# gleis-a-3.net
KiCad netlist of a schematic drawn in EAGLE
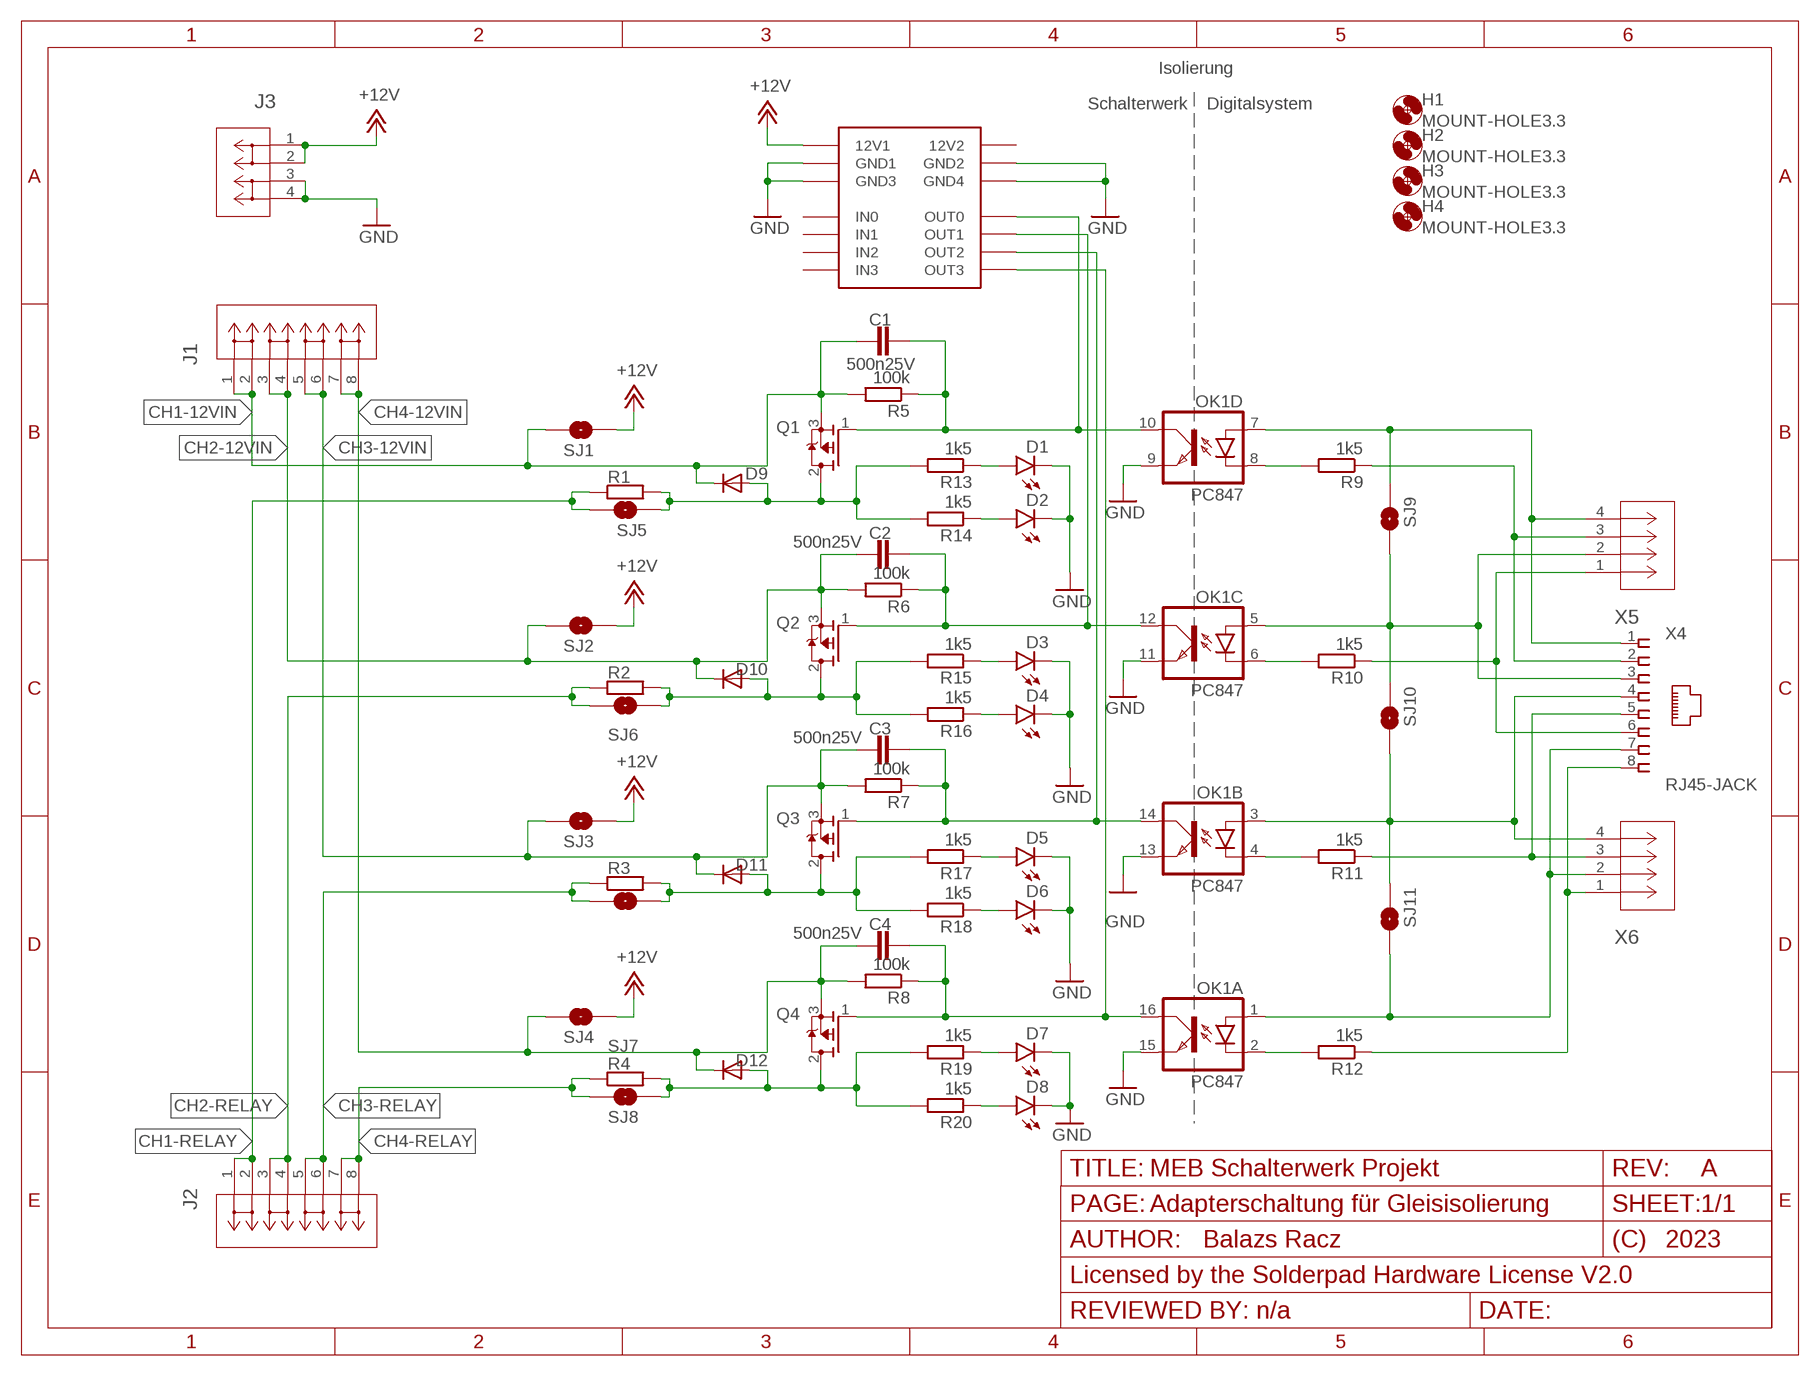
[diagram p0: schematic, sheet 1]

(export (version "E")
  (design (tool "Eeschema 10.0.6"))
  (components
    (comp (ref "C1")
      (value "500n25V")
      (footprint "eagle-import:C0805")
      (libsource (lib "eagle-import") (part "C-EUC0805"))
    )
    (comp (ref "C2")
      (value "500n25V")
      (footprint "eagle-import:C0805")
      (libsource (lib "eagle-import") (part "C-EUC0805"))
    )
    (comp (ref "C3")
      (value "500n25V")
      (footprint "eagle-import:C0805")
      (libsource (lib "eagle-import") (part "C-EUC0805"))
    )
    (comp (ref "C4")
      (value "500n25V")
      (footprint "eagle-import:C0805")
      (libsource (lib "eagle-import") (part "C-EUC0805"))
    )
    (comp (ref "D1")
      (value "LEDCHIPLED_0603")
      (footprint "eagle-import:CHIPLED_0603")
      (libsource (lib "eagle-import") (part "LEDCHIPLED_0603"))
    )
    (comp (ref "D2")
      (value "LEDHEADER")
      (footprint "eagle-import:LEDHEADER")
      (libsource (lib "eagle-import") (part "LEDHEADER"))
    )
    (comp (ref "D3")
      (value "LEDCHIPLED_0603")
      (footprint "eagle-import:CHIPLED_0603")
      (libsource (lib "eagle-import") (part "LEDCHIPLED_0603"))
    )
    (comp (ref "D4")
      (value "LEDHEADER")
      (footprint "eagle-import:LEDHEADER")
      (libsource (lib "eagle-import") (part "LEDHEADER"))
    )
    (comp (ref "D5")
      (value "LEDCHIPLED_0603")
      (footprint "eagle-import:CHIPLED_0603")
      (libsource (lib "eagle-import") (part "LEDCHIPLED_0603"))
    )
    (comp (ref "D6")
      (value "LEDHEADER")
      (footprint "eagle-import:LEDHEADER")
      (libsource (lib "eagle-import") (part "LEDHEADER"))
    )
    (comp (ref "D7")
      (value "LEDCHIPLED_0603")
      (footprint "eagle-import:CHIPLED_0603")
      (libsource (lib "eagle-import") (part "LEDCHIPLED_0603"))
    )
    (comp (ref "D8")
      (value "LEDHEADER")
      (footprint "eagle-import:LEDHEADER")
      (libsource (lib "eagle-import") (part "LEDHEADER"))
    )
    (comp (ref "D9")
      (value "DIODEDO-214AA-NODOC")
      (footprint "eagle-import:DO214AA-NODOC")
      (libsource (lib "eagle-import") (part "DIODEDO-214AA-NODOC"))
    )
    (comp (ref "D10")
      (value "DIODEDO-214AA-NODOC")
      (footprint "eagle-import:DO214AA-NODOC")
      (libsource (lib "eagle-import") (part "DIODEDO-214AA-NODOC"))
    )
    (comp (ref "D11")
      (value "DIODEDO-214AA-NODOC")
      (footprint "eagle-import:DO214AA-NODOC")
      (libsource (lib "eagle-import") (part "DIODEDO-214AA-NODOC"))
    )
    (comp (ref "D12")
      (value "DIODEDO-214AA-NODOC")
      (footprint "eagle-import:DO214AA-NODOC")
      (libsource (lib "eagle-import") (part "DIODEDO-214AA-NODOC"))
    )
    (comp (ref "H1")
      (value "MOUNT-HOLE3.3")
      (footprint "eagle-import:3,3")
      (libsource (lib "eagle-import") (part "MOUNT-HOLE3.3"))
    )
    (comp (ref "H2")
      (value "MOUNT-HOLE3.3")
      (footprint "eagle-import:3,3")
      (libsource (lib "eagle-import") (part "MOUNT-HOLE3.3"))
    )
    (comp (ref "H3")
      (value "MOUNT-HOLE3.3")
      (footprint "eagle-import:3,3")
      (libsource (lib "eagle-import") (part "MOUNT-HOLE3.3"))
    )
    (comp (ref "H4")
      (value "MOUNT-HOLE3.3")
      (footprint "eagle-import:3,3")
      (libsource (lib "eagle-import") (part "MOUNT-HOLE3.3"))
    )
    (comp (ref "J1")
      (value "PHNX_4P_508CONN_1017493")
      (footprint "eagle-import:PHNX_4P_508")
      (fields
        (field (name "MANUFACTURER_PART_NUMBER") "1017505")
        (field (name "COPYRIGHT") "Copyright (C) 2023 Ultra Librarian. All rights reserved.")
      )
      (libsource (lib "eagle-import") (part "PHNX_4P_508CONN_1017493"))
    )
    (comp (ref "J2")
      (value "PHNX_4P_508CONN_1017493")
      (footprint "eagle-import:PHNX_4P_508")
      (fields
        (field (name "MANUFACTURER_PART_NUMBER") "1017505")
        (field (name "COPYRIGHT") "Copyright (C) 2023 Ultra Librarian. All rights reserved.")
      )
      (libsource (lib "eagle-import") (part "PHNX_4P_508CONN_1017493"))
    )
    (comp (ref "J3")
      (value "PHNX_2P_508CONN_1017491")
      (footprint "eagle-import:PHNX_2P_508")
      (fields
        (field (name "MANUFACTURER_PART_NUMBER") "1017503")
        (field (name "COPYRIGHT") "Copyright (C) 2023 Ultra Librarian. All rights reserved.")
      )
      (libsource (lib "eagle-import") (part "PHNX_2P_508CONN_1017491"))
    )
    (comp (ref "OK1")
      (value "PC847")
      (footprint "eagle-import:DIL16")
      (libsource (lib "eagle-import") (part "PC847"))
    )
    (comp (ref "Q1")
      (value "P-MOSFET")
      (footprint "eagle-import:DPAK-2")
      (fields (field (name "MANUFACTURER") "Infineon"))
      (libsource (lib "eagle-import") (part "P-MOSFET"))
    )
    (comp (ref "Q2")
      (value "P-MOSFET")
      (footprint "eagle-import:DPAK-2")
      (fields (field (name "MANUFACTURER") "Infineon"))
      (libsource (lib "eagle-import") (part "P-MOSFET"))
    )
    (comp (ref "Q3")
      (value "P-MOSFET")
      (footprint "eagle-import:DPAK-2")
      (fields (field (name "MANUFACTURER") "Infineon"))
      (libsource (lib "eagle-import") (part "P-MOSFET"))
    )
    (comp (ref "Q4")
      (value "P-MOSFET")
      (footprint "eagle-import:DPAK-2")
      (fields (field (name "MANUFACTURER") "Infineon"))
      (libsource (lib "eagle-import") (part "P-MOSFET"))
    )
    (comp (ref "R1")
      (value "R-EU_VTA52")
      (footprint "eagle-import:VTA52")
      (libsource (lib "eagle-import") (part "R-EU_VTA52"))
    )
    (comp (ref "R2")
      (value "R-EU_VTA52")
      (footprint "eagle-import:VTA52")
      (libsource (lib "eagle-import") (part "R-EU_VTA52"))
    )
    (comp (ref "R3")
      (value "R-EU_VTA52")
      (footprint "eagle-import:VTA52")
      (libsource (lib "eagle-import") (part "R-EU_VTA52"))
    )
    (comp (ref "R4")
      (value "R-EU_VTA52")
      (footprint "eagle-import:VTA52")
      (libsource (lib "eagle-import") (part "R-EU_VTA52"))
    )
    (comp (ref "R5")
      (value "100k")
      (footprint "eagle-import:R0805")
      (libsource (lib "eagle-import") (part "R-EU_R0805"))
    )
    (comp (ref "R6")
      (value "100k")
      (footprint "eagle-import:R0805")
      (libsource (lib "eagle-import") (part "R-EU_R0805"))
    )
    (comp (ref "R7")
      (value "100k")
      (footprint "eagle-import:R0805")
      (libsource (lib "eagle-import") (part "R-EU_R0805"))
    )
    (comp (ref "R8")
      (value "100k")
      (footprint "eagle-import:R0805")
      (libsource (lib "eagle-import") (part "R-EU_R0805"))
    )
    (comp (ref "R9")
      (value "1k5")
      (footprint "eagle-import:R0805")
      (libsource (lib "eagle-import") (part "R-EU_R0805"))
    )
    (comp (ref "R10")
      (value "1k5")
      (footprint "eagle-import:R0805")
      (libsource (lib "eagle-import") (part "R-EU_R0805"))
    )
    (comp (ref "R11")
      (value "1k5")
      (footprint "eagle-import:R0805")
      (libsource (lib "eagle-import") (part "R-EU_R0805"))
    )
    (comp (ref "R12")
      (value "1k5")
      (footprint "eagle-import:R0805")
      (libsource (lib "eagle-import") (part "R-EU_R0805"))
    )
    (comp (ref "R13")
      (value "1k5")
      (footprint "eagle-import:R0805")
      (libsource (lib "eagle-import") (part "R-EU_R0805"))
    )
    (comp (ref "R14")
      (value "1k5")
      (footprint "eagle-import:R0805")
      (libsource (lib "eagle-import") (part "R-EU_R0805"))
    )
    (comp (ref "R15")
      (value "1k5")
      (footprint "eagle-import:R0805")
      (libsource (lib "eagle-import") (part "R-EU_R0805"))
    )
    (comp (ref "R16")
      (value "1k5")
      (footprint "eagle-import:R0805")
      (libsource (lib "eagle-import") (part "R-EU_R0805"))
    )
    (comp (ref "R17")
      (value "1k5")
      (footprint "eagle-import:R0805")
      (libsource (lib "eagle-import") (part "R-EU_R0805"))
    )
    (comp (ref "R18")
      (value "1k5")
      (footprint "eagle-import:R0805")
      (libsource (lib "eagle-import") (part "R-EU_R0805"))
    )
    (comp (ref "R19")
      (value "1k5")
      (footprint "eagle-import:R0805")
      (libsource (lib "eagle-import") (part "R-EU_R0805"))
    )
    (comp (ref "R20")
      (value "1k5")
      (footprint "eagle-import:R0805")
      (libsource (lib "eagle-import") (part "R-EU_R0805"))
    )
    (comp (ref "SJ1")
      (value "SJRND2")
      (footprint "eagle-import:SJ_RND2")
      (libsource (lib "eagle-import") (part "SJRND2"))
    )
    (comp (ref "SJ2")
      (value "SJRND2")
      (footprint "eagle-import:SJ_RND2")
      (libsource (lib "eagle-import") (part "SJRND2"))
    )
    (comp (ref "SJ3")
      (value "SJRND2")
      (footprint "eagle-import:SJ_RND2")
      (libsource (lib "eagle-import") (part "SJRND2"))
    )
    (comp (ref "SJ4")
      (value "SJRND2")
      (footprint "eagle-import:SJ_RND2")
      (libsource (lib "eagle-import") (part "SJRND2"))
    )
    (comp (ref "SJ5")
      (value "SJRND2")
      (footprint "eagle-import:SJ_RND2")
      (libsource (lib "eagle-import") (part "SJRND2"))
    )
    (comp (ref "SJ6")
      (value "SJRND2")
      (footprint "eagle-import:SJ_RND2")
      (libsource (lib "eagle-import") (part "SJRND2"))
    )
    (comp (ref "SJ7")
      (value "SJRND2")
      (footprint "eagle-import:SJ_RND2")
      (libsource (lib "eagle-import") (part "SJRND2"))
    )
    (comp (ref "SJ8")
      (value "SJRND2")
      (footprint "eagle-import:SJ_RND2")
      (libsource (lib "eagle-import") (part "SJRND2"))
    )
    (comp (ref "SJ9")
      (value "SJRND2")
      (footprint "eagle-import:SJ_RND2")
      (libsource (lib "eagle-import") (part "SJRND2"))
    )
    (comp (ref "SJ10")
      (value "SJRND2")
      (footprint "eagle-import:SJ_RND2")
      (libsource (lib "eagle-import") (part "SJRND2"))
    )
    (comp (ref "SJ11")
      (value "SJRND2")
      (footprint "eagle-import:SJ_RND2")
      (libsource (lib "eagle-import") (part "SJRND2"))
    )
    (comp (ref "X2")
      (value "IO-HAT")
      (footprint "eagle-import:IOBOARD")
      (libsource (lib "eagle-import") (part "IO-HAT"))
    )
    (comp (ref "X4")
      (value "RJ45-JACK")
      (footprint "eagle-import:RJ45-PULSE-E5J88")
      (libsource (lib "eagle-import") (part "RJ45-JACKRJ45-PULSE-E5J00"))
    )
    (comp (ref "X5")
      (value "PHNX_4P_350CONN_1984989_PXC")
      (footprint "eagle-import:PHNX_4P_350")
      (fields
        (field (name "MANUFACTURER_PART_NUMBER") "1984989")
        (field (name "COPYRIGHT") "Copyright (C) 2023 Ultra Librarian. All rights reserved.")
      )
      (libsource (lib "eagle-import") (part "PHNX_4P_350CONN_1984989_PXC"))
    )
    (comp (ref "X6")
      (value "PHNX_4P_350CONN_1984989_PXC")
      (footprint "eagle-import:PHNX_4P_350")
      (fields
        (field (name "MANUFACTURER_PART_NUMBER") "1984989")
        (field (name "COPYRIGHT") "Copyright (C) 2023 Ultra Librarian. All rights reserved.")
      )
      (libsource (lib "eagle-import") (part "PHNX_4P_350CONN_1984989_PXC"))
    )
  )
  (nets
    (net (code "1") (name "+12V") (class "Default")
      (node (ref "J3") (pin "1") (pinfunction "1_1") (pintype "passive"))
      (node (ref "J3") (pin "2") (pinfunction "2_2") (pintype "passive"))
      (node (ref "SJ1") (pin "P$2") (pinfunction "2_P$2") (pintype "passive"))
      (node (ref "SJ2") (pin "P$2") (pinfunction "2_P$2") (pintype "passive"))
      (node (ref "SJ3") (pin "P$2") (pinfunction "2_P$2") (pintype "passive"))
      (node (ref "SJ4") (pin "P$2") (pinfunction "2_P$2") (pintype "passive"))
      (node (ref "X2") (pin "P$1") (pinfunction "12V1_P$1") (pintype "power_in"))
    )
    (net (code "2") (name "/12V2") (class "Default")
      (node (ref "X2") (pin "P$22") (pinfunction "12V2_P$22") (pintype "power_in"))
    )
    (net (code "3") (name "CH1-12VIN") (class "Default")
      (node (ref "C1") (pin "1") (pinfunction "1_1") (pintype "passive"))
      (node (ref "D9") (pin "C") (pinfunction "C_C") (pintype "passive"))
      (node (ref "J1") (pin "1") (pinfunction "1_1") (pintype "passive"))
      (node (ref "J1") (pin "2") (pinfunction "2_2") (pintype "passive"))
      (node (ref "Q1") (pin "3") (pinfunction "S_3") (pintype "passive"))
      (node (ref "R5") (pin "2") (pinfunction "2_2") (pintype "passive"))
      (node (ref "SJ1") (pin "P$1") (pinfunction "1_P$1") (pintype "passive"))
    )
    (net (code "4") (name "CH1-RELAY") (class "Default")
      (node (ref "J2") (pin "1") (pinfunction "1_1") (pintype "passive"))
      (node (ref "J2") (pin "2") (pinfunction "2_2") (pintype "passive"))
      (node (ref "R1") (pin "1") (pinfunction "1_1") (pintype "passive"))
      (node (ref "SJ5") (pin "P$1") (pinfunction "1_P$1") (pintype "passive"))
    )
    (net (code "5") (name "CH2-12VIN") (class "Default")
      (node (ref "C2") (pin "1") (pinfunction "1_1") (pintype "passive"))
      (node (ref "D10") (pin "C") (pinfunction "C_C") (pintype "passive"))
      (node (ref "J1") (pin "3") (pinfunction "3_3") (pintype "passive"))
      (node (ref "J1") (pin "4") (pinfunction "4_4") (pintype "passive"))
      (node (ref "Q2") (pin "3") (pinfunction "S_3") (pintype "passive"))
      (node (ref "R6") (pin "2") (pinfunction "2_2") (pintype "passive"))
      (node (ref "SJ2") (pin "P$1") (pinfunction "1_P$1") (pintype "passive"))
    )
    (net (code "6") (name "CH2-RELAY") (class "Default")
      (node (ref "J2") (pin "3") (pinfunction "3_3") (pintype "passive"))
      (node (ref "J2") (pin "4") (pinfunction "4_4") (pintype "passive"))
      (node (ref "R2") (pin "1") (pinfunction "1_1") (pintype "passive"))
      (node (ref "SJ6") (pin "P$1") (pinfunction "1_P$1") (pintype "passive"))
    )
    (net (code "7") (name "CH3-12VIN") (class "Default")
      (node (ref "C3") (pin "1") (pinfunction "1_1") (pintype "passive"))
      (node (ref "D11") (pin "C") (pinfunction "C_C") (pintype "passive"))
      (node (ref "J1") (pin "5") (pinfunction "5_5") (pintype "passive"))
      (node (ref "J1") (pin "6") (pinfunction "6_6") (pintype "passive"))
      (node (ref "Q3") (pin "3") (pinfunction "S_3") (pintype "passive"))
      (node (ref "R7") (pin "2") (pinfunction "2_2") (pintype "passive"))
      (node (ref "SJ3") (pin "P$1") (pinfunction "1_P$1") (pintype "passive"))
    )
    (net (code "8") (name "CH3-RELAY") (class "Default")
      (node (ref "J2") (pin "5") (pinfunction "5_5") (pintype "passive"))
      (node (ref "J2") (pin "6") (pinfunction "6_6") (pintype "passive"))
      (node (ref "R3") (pin "1") (pinfunction "1_1") (pintype "passive"))
      (node (ref "SJ7") (pin "P$1") (pinfunction "1_P$1") (pintype "passive"))
    )
    (net (code "9") (name "CH4-12VIN") (class "Default")
      (node (ref "C4") (pin "1") (pinfunction "1_1") (pintype "passive"))
      (node (ref "D12") (pin "C") (pinfunction "C_C") (pintype "passive"))
      (node (ref "J1") (pin "7") (pinfunction "7_7") (pintype "passive"))
      (node (ref "J1") (pin "8") (pinfunction "8_8") (pintype "passive"))
      (node (ref "Q4") (pin "3") (pinfunction "S_3") (pintype "passive"))
      (node (ref "R8") (pin "2") (pinfunction "2_2") (pintype "passive"))
      (node (ref "SJ4") (pin "P$1") (pinfunction "1_P$1") (pintype "passive"))
    )
    (net (code "10") (name "CH4-RELAY") (class "Default")
      (node (ref "J2") (pin "7") (pinfunction "7_7") (pintype "passive"))
      (node (ref "J2") (pin "8") (pinfunction "8_8") (pintype "passive"))
      (node (ref "R4") (pin "1") (pinfunction "1_1") (pintype "passive"))
      (node (ref "SJ8") (pin "P$1") (pinfunction "1_P$1") (pintype "passive"))
    )
    (net (code "11") (name "GND") (class "Default")
      (node (ref "D1") (pin "C") (pinfunction "C_C") (pintype "passive"))
      (node (ref "D2") (pin "C") (pinfunction "C_C") (pintype "passive"))
      (node (ref "D3") (pin "C") (pinfunction "C_C") (pintype "passive"))
      (node (ref "D4") (pin "C") (pinfunction "C_C") (pintype "passive"))
      (node (ref "D5") (pin "C") (pinfunction "C_C") (pintype "passive"))
      (node (ref "D6") (pin "C") (pinfunction "C_C") (pintype "passive"))
      (node (ref "D7") (pin "C") (pinfunction "C_C") (pintype "passive"))
      (node (ref "D8") (pin "C") (pinfunction "C_C") (pintype "passive"))
      (node (ref "J3") (pin "3") (pinfunction "3_3") (pintype "passive"))
      (node (ref "J3") (pin "4") (pinfunction "4_4") (pintype "passive"))
      (node (ref "OK1") (pin "11") (pinfunction "EMIT_11") (pintype "passive"))
      (node (ref "OK1") (pin "13") (pinfunction "EMIT_13") (pintype "passive"))
      (node (ref "OK1") (pin "15") (pinfunction "EMIT_15") (pintype "passive"))
      (node (ref "OK1") (pin "9") (pinfunction "EMIT_9") (pintype "passive"))
      (node (ref "X2") (pin "P$11") (pinfunction "GND3_P$11") (pintype "power_in"))
      (node (ref "X2") (pin "P$12") (pinfunction "GND4_P$12") (pintype "power_in"))
      (node (ref "X2") (pin "P$2") (pinfunction "GND1_P$2") (pintype "power_in"))
      (node (ref "X2") (pin "P$21") (pinfunction "GND2_P$21") (pintype "power_in"))
    )
    (net (code "12") (name "Net-(D1-PadA)") (class "Default")
      (node (ref "D1") (pin "A") (pinfunction "A_A") (pintype "passive"))
      (node (ref "R13") (pin "1") (pinfunction "1_1") (pintype "passive"))
    )
    (net (code "13") (name "Net-(D2-PadA)") (class "Default")
      (node (ref "D2") (pin "A") (pinfunction "A_A") (pintype "passive"))
      (node (ref "R14") (pin "1") (pinfunction "1_1") (pintype "passive"))
    )
    (net (code "14") (name "Net-(D3-PadA)") (class "Default")
      (node (ref "D3") (pin "A") (pinfunction "A_A") (pintype "passive"))
      (node (ref "R15") (pin "1") (pinfunction "1_1") (pintype "passive"))
    )
    (net (code "15") (name "Net-(D4-PadA)") (class "Default")
      (node (ref "D4") (pin "A") (pinfunction "A_A") (pintype "passive"))
      (node (ref "R16") (pin "1") (pinfunction "1_1") (pintype "passive"))
    )
    (net (code "16") (name "Net-(D5-PadA)") (class "Default")
      (node (ref "D5") (pin "A") (pinfunction "A_A") (pintype "passive"))
      (node (ref "R17") (pin "1") (pinfunction "1_1") (pintype "passive"))
    )
    (net (code "17") (name "Net-(D6-PadA)") (class "Default")
      (node (ref "D6") (pin "A") (pinfunction "A_A") (pintype "passive"))
      (node (ref "R18") (pin "1") (pinfunction "1_1") (pintype "passive"))
    )
    (net (code "18") (name "Net-(D7-PadA)") (class "Default")
      (node (ref "D7") (pin "A") (pinfunction "A_A") (pintype "passive"))
      (node (ref "R19") (pin "1") (pinfunction "1_1") (pintype "passive"))
    )
    (net (code "19") (name "Net-(D8-PadA)") (class "Default")
      (node (ref "D8") (pin "A") (pinfunction "A_A") (pintype "passive"))
      (node (ref "R20") (pin "1") (pinfunction "1_1") (pintype "passive"))
    )
    (net (code "20") (name "Net-(OK1A-A)") (class "Default")
      (node (ref "OK1") (pin "1") (pinfunction "A_1") (pintype "passive"))
      (node (ref "SJ11") (pin "P$1") (pinfunction "1_P$1") (pintype "passive"))
      (node (ref "X4") (pin "7") (pinfunction "7_7") (pintype "passive"))
      (node (ref "X6") (pin "2") (pinfunction "2_2") (pintype "passive"))
    )
    (net (code "21") (name "Net-(OK1A-C)") (class "Default")
      (node (ref "OK1") (pin "2") (pinfunction "C_2") (pintype "passive"))
      (node (ref "R12") (pin "2") (pinfunction "2_2") (pintype "passive"))
    )
    (net (code "22") (name "Net-(OK1A-COL)") (class "Default")
      (node (ref "C4") (pin "2") (pinfunction "2_2") (pintype "passive"))
      (node (ref "OK1") (pin "16") (pinfunction "COL_16") (pintype "passive"))
      (node (ref "Q4") (pin "1") (pinfunction "G_1") (pintype "passive"))
      (node (ref "R8") (pin "1") (pinfunction "1_1") (pintype "passive"))
      (node (ref "X2") (pin "P$17") (pinfunction "OUT3_P$17") (pintype "open_collector"))
    )
    (net (code "23") (name "Net-(OK1B-A)") (class "Default")
      (node (ref "OK1") (pin "3") (pinfunction "A_3") (pintype "passive"))
      (node (ref "SJ10") (pin "P$1") (pinfunction "1_P$1") (pintype "passive"))
      (node (ref "SJ11") (pin "P$2") (pinfunction "2_P$2") (pintype "passive"))
      (node (ref "X4") (pin "4") (pinfunction "4_4") (pintype "passive"))
      (node (ref "X6") (pin "4") (pinfunction "4_4") (pintype "passive"))
    )
    (net (code "24") (name "Net-(OK1B-C)") (class "Default")
      (node (ref "OK1") (pin "4") (pinfunction "C_4") (pintype "passive"))
      (node (ref "R11") (pin "2") (pinfunction "2_2") (pintype "passive"))
    )
    (net (code "25") (name "Net-(OK1B-COL)") (class "Default")
      (node (ref "C3") (pin "2") (pinfunction "2_2") (pintype "passive"))
      (node (ref "OK1") (pin "14") (pinfunction "COL_14") (pintype "passive"))
      (node (ref "Q3") (pin "1") (pinfunction "G_1") (pintype "passive"))
      (node (ref "R7") (pin "1") (pinfunction "1_1") (pintype "passive"))
      (node (ref "X2") (pin "P$18") (pinfunction "OUT2_P$18") (pintype "open_collector"))
    )
    (net (code "26") (name "Net-(OK1C-A)") (class "Default")
      (node (ref "OK1") (pin "5") (pinfunction "A_5") (pintype "passive"))
      (node (ref "SJ10") (pin "P$2") (pinfunction "2_P$2") (pintype "passive"))
      (node (ref "SJ9") (pin "P$1") (pinfunction "1_P$1") (pintype "passive"))
      (node (ref "X4") (pin "3") (pinfunction "3_3") (pintype "passive"))
      (node (ref "X5") (pin "2") (pinfunction "2_2") (pintype "passive"))
    )
    (net (code "27") (name "Net-(OK1C-C)") (class "Default")
      (node (ref "OK1") (pin "6") (pinfunction "C_6") (pintype "passive"))
      (node (ref "R10") (pin "2") (pinfunction "2_2") (pintype "passive"))
    )
    (net (code "28") (name "Net-(OK1C-COL)") (class "Default")
      (node (ref "C2") (pin "2") (pinfunction "2_2") (pintype "passive"))
      (node (ref "OK1") (pin "12") (pinfunction "COL_12") (pintype "passive"))
      (node (ref "Q2") (pin "1") (pinfunction "G_1") (pintype "passive"))
      (node (ref "R6") (pin "1") (pinfunction "1_1") (pintype "passive"))
      (node (ref "X2") (pin "P$19") (pinfunction "OUT1_P$19") (pintype "open_collector"))
    )
    (net (code "29") (name "Net-(OK1D-A)") (class "Default")
      (node (ref "OK1") (pin "7") (pinfunction "A_7") (pintype "passive"))
      (node (ref "SJ9") (pin "P$2") (pinfunction "2_P$2") (pintype "passive"))
      (node (ref "X4") (pin "1") (pinfunction "1_1") (pintype "passive"))
      (node (ref "X5") (pin "4") (pinfunction "4_4") (pintype "passive"))
    )
    (net (code "30") (name "Net-(OK1D-C)") (class "Default")
      (node (ref "OK1") (pin "8") (pinfunction "C_8") (pintype "passive"))
      (node (ref "R9") (pin "2") (pinfunction "2_2") (pintype "passive"))
    )
    (net (code "31") (name "Net-(OK1D-COL)") (class "Default")
      (node (ref "C1") (pin "2") (pinfunction "2_2") (pintype "passive"))
      (node (ref "OK1") (pin "10") (pinfunction "COL_10") (pintype "passive"))
      (node (ref "Q1") (pin "1") (pinfunction "G_1") (pintype "passive"))
      (node (ref "R5") (pin "1") (pinfunction "1_1") (pintype "passive"))
      (node (ref "X2") (pin "P$20") (pinfunction "OUT0_P$20") (pintype "open_collector"))
    )
    (net (code "32") (name "Net-(Q1-D)") (class "Default")
      (node (ref "D9") (pin "A") (pinfunction "A_A") (pintype "passive"))
      (node (ref "Q1") (pin "2") (pinfunction "D_2") (pintype "passive"))
      (node (ref "R1") (pin "2") (pinfunction "2_2") (pintype "passive"))
      (node (ref "R13") (pin "2") (pinfunction "2_2") (pintype "passive"))
      (node (ref "R14") (pin "2") (pinfunction "2_2") (pintype "passive"))
      (node (ref "SJ5") (pin "P$2") (pinfunction "2_P$2") (pintype "passive"))
    )
    (net (code "33") (name "Net-(Q2-D)") (class "Default")
      (node (ref "D10") (pin "A") (pinfunction "A_A") (pintype "passive"))
      (node (ref "Q2") (pin "2") (pinfunction "D_2") (pintype "passive"))
      (node (ref "R15") (pin "2") (pinfunction "2_2") (pintype "passive"))
      (node (ref "R16") (pin "2") (pinfunction "2_2") (pintype "passive"))
      (node (ref "R2") (pin "2") (pinfunction "2_2") (pintype "passive"))
      (node (ref "SJ6") (pin "P$2") (pinfunction "2_P$2") (pintype "passive"))
    )
    (net (code "34") (name "Net-(Q3-D)") (class "Default")
      (node (ref "D11") (pin "A") (pinfunction "A_A") (pintype "passive"))
      (node (ref "Q3") (pin "2") (pinfunction "D_2") (pintype "passive"))
      (node (ref "R17") (pin "2") (pinfunction "2_2") (pintype "passive"))
      (node (ref "R18") (pin "2") (pinfunction "2_2") (pintype "passive"))
      (node (ref "R3") (pin "2") (pinfunction "2_2") (pintype "passive"))
      (node (ref "SJ7") (pin "P$2") (pinfunction "2_P$2") (pintype "passive"))
    )
    (net (code "35") (name "Net-(Q4-D)") (class "Default")
      (node (ref "D12") (pin "A") (pinfunction "A_A") (pintype "passive"))
      (node (ref "Q4") (pin "2") (pinfunction "D_2") (pintype "passive"))
      (node (ref "R19") (pin "2") (pinfunction "2_2") (pintype "passive"))
      (node (ref "R20") (pin "2") (pinfunction "2_2") (pintype "passive"))
      (node (ref "R4") (pin "2") (pinfunction "2_2") (pintype "passive"))
      (node (ref "SJ8") (pin "P$2") (pinfunction "2_P$2") (pintype "passive"))
    )
    (net (code "36") (name "Net-(R9-Pad1)") (class "Default")
      (node (ref "R9") (pin "1") (pinfunction "1_1") (pintype "passive"))
      (node (ref "X4") (pin "2") (pinfunction "2_2") (pintype "passive"))
      (node (ref "X5") (pin "3") (pinfunction "3_3") (pintype "passive"))
    )
    (net (code "37") (name "Net-(R10-Pad1)") (class "Default")
      (node (ref "R10") (pin "1") (pinfunction "1_1") (pintype "passive"))
      (node (ref "X4") (pin "6") (pinfunction "6_6") (pintype "passive"))
      (node (ref "X5") (pin "1") (pinfunction "1_1") (pintype "passive"))
    )
    (net (code "38") (name "Net-(R11-Pad1)") (class "Default")
      (node (ref "R11") (pin "1") (pinfunction "1_1") (pintype "passive"))
      (node (ref "X4") (pin "5") (pinfunction "5_5") (pintype "passive"))
      (node (ref "X6") (pin "3") (pinfunction "3_3") (pintype "passive"))
    )
    (net (code "39") (name "Net-(R12-Pad1)") (class "Default")
      (node (ref "R12") (pin "1") (pinfunction "1_1") (pintype "passive"))
      (node (ref "X4") (pin "8") (pinfunction "8_8") (pintype "passive"))
      (node (ref "X6") (pin "1") (pinfunction "1_1") (pintype "passive"))
    )
    (net (code "40") (name "unconnected-(X2A-IN0-PadP$3)") (class "Default")
      (node (ref "X2") (pin "P$3") (pinfunction "IN0_P$3") (pintype "input"))
    )
    (net (code "41") (name "unconnected-(X2A-IN1-PadP$4)") (class "Default")
      (node (ref "X2") (pin "P$4") (pinfunction "IN1_P$4") (pintype "input"))
    )
    (net (code "42") (name "unconnected-(X2A-IN2-PadP$5)") (class "Default")
      (node (ref "X2") (pin "P$5") (pinfunction "IN2_P$5") (pintype "input"))
    )
    (net (code "43") (name "unconnected-(X2A-IN3-PadP$6)") (class "Default")
      (node (ref "X2") (pin "P$6") (pinfunction "IN3_P$6") (pintype "input"))
    )
  )
)
